# P09_Ethernet.net
KiCad netlist of a schematic drawn in Altium Designer
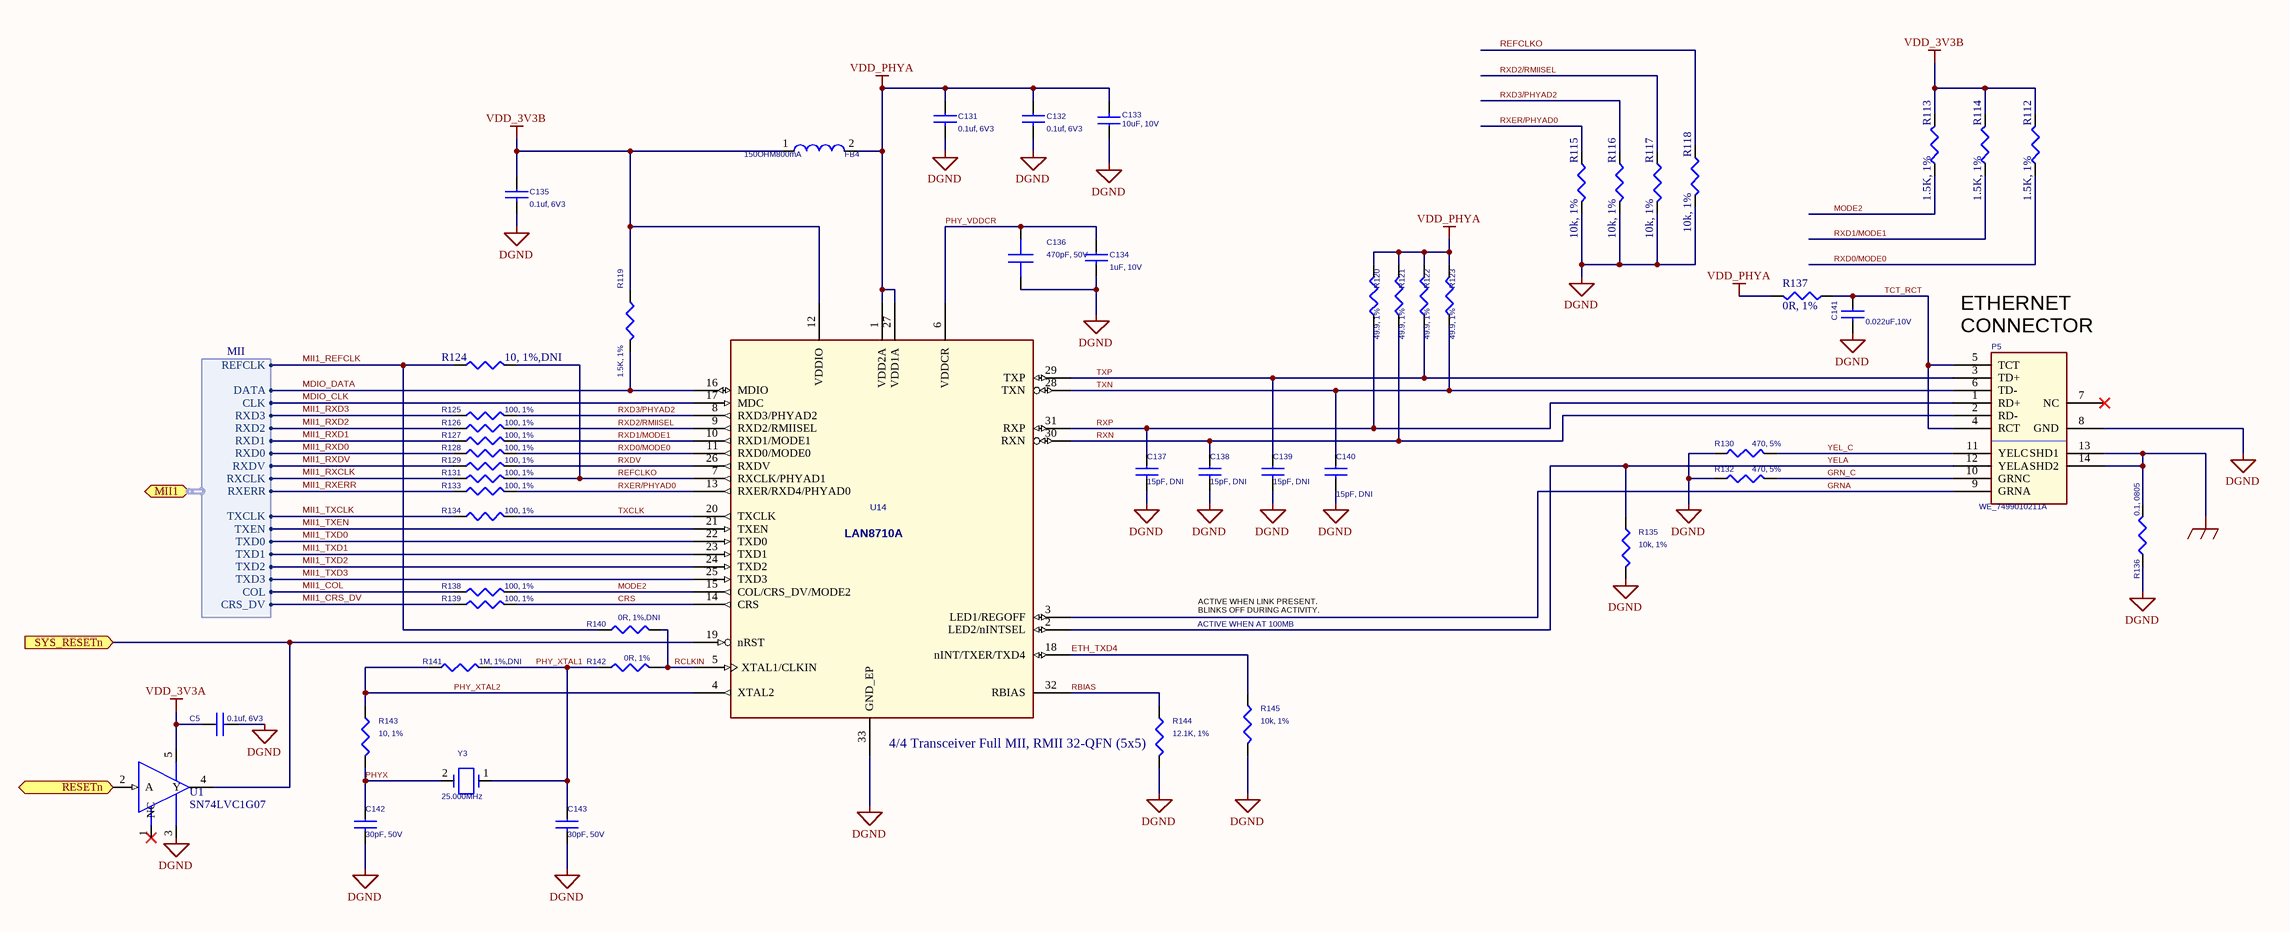
[diagram p0: P09_Ethernet.SchDoc]

(export (version "E")
  (design (tool "Eeschema 10.0.6"))
  (components
    (comp (ref "C5")
      (value "0.1uf, 6V3")
      (footprint "402")
      (description "CAP CER 0.1UF 6.3V 10% X5R 0402")
      (fields
        (field (name "MANUFACTURER") "TDK Corporation")
        (field (name "MANUFACTURER PART NUMBER") "C1005X5R0J104K050BA")
      )
      (libsource (lib "BEAGLEBONEBLACK_REV A5B") (part "CAP_0.1uF_X7R_16V_10% 0402"))
    )
    (comp (ref "C131")
      (value "0.1uf, 6V3")
      (footprint "402")
      (description "CAP CER 0.1UF 6.3V 10% X5R 0402")
      (fields
        (field (name "MANUFACTURER") "TDK Corporation")
        (field (name "MANUFACTURER PART NUMBER") "C1005X5R0J104K050BA")
      )
      (libsource (lib "BEAGLEBONEBLACK_REV A5B") (part "CAP_0.1uF_X7R_16V_10% 0402"))
    )
    (comp (ref "C132")
      (value "0.1uf, 6V3")
      (footprint "402")
      (description "CAP CER 0.1UF 6.3V 10% X5R 0402")
      (fields
        (field (name "MANUFACTURER") "TDK Corporation")
        (field (name "MANUFACTURER PART NUMBER") "C1005X5R0J104K050BA")
      )
      (libsource (lib "BEAGLEBONEBLACK_REV A5B") (part "CAP_0.1uF_X7R_16V_10% 0402"))
    )
    (comp (ref "C133")
      (value "10uF, 10V")
      (footprint "805")
      (description "CAP CER 10UF 10V Y5V 0805")
      (fields
        (field (name "MANUFACTURER") "TDK Corporation")
        (field (name "MANUFACTURER PART NUMBER") "C2012Y5V1A106Z")
      )
      (libsource (lib "BEAGLEBONEBLACK_REV A5B") (part "CAP_4.7uF_X5R_6.3V_10%_0603"))
    )
    (comp (ref "C134")
      (value "1uF, 10V")
      (footprint "402")
      (description "CAP CER 1UF 10V 10% X5R 0402")
      (fields
        (field (name "MANUFACTURER") "AVX Corporation")
        (field (name "MANUFACTURER PART NUMBER") "0402ZD105KAT2A")
      )
      (libsource (lib "BEAGLEBONEBLACK_REV A5B") (part "CAP_1.0UF_X5R_10V_10%_0402"))
    )
    (comp (ref "C135")
      (value "0.1uf, 6V3")
      (footprint "402")
      (description "CAP CER 0.1UF 6.3V 10% X5R 0402")
      (fields
        (field (name "MANUFACTURER") "TDK Corporation")
        (field (name "MANUFACTURER PART NUMBER") "C1005X5R0J104K050BA")
      )
      (libsource (lib "BEAGLEBONEBLACK_REV A5B") (part "CAP_0.1uF_X7R_16V_10% 0402"))
    )
    (comp (ref "C136")
      (value "470pF, 50V")
      (footprint "402")
      (description "CAP CER 470PF 50V 10% X7R 0402")
      (fields
        (field (name "MANUFACTURER") "Murata Electronics North America")
        (field (name "MANUFACTURER PART NUMBER") "GRM155R71H471KA01D")
      )
      (libsource (lib "BEAGLEBONEBLACK_REV A5B") (part "470pF/5%/50V/C0G/0603_0"))
    )
    (comp (ref "C137")
      (value "15pF, DNI")
      (footprint "402")
      (description "CAP CER 15PF 50V 5% NP0 0402")
      (fields
        (field (name "MANUFACTURER") "TDK Corporation")
        (field (name "MANUFACTURER PART NUMBER") "C1005C0G1H150J050BA")
      )
      (libsource (lib "BEAGLEBONEBLACK_REV A5B") (part "CAP_0402_100pF_COG_50V"))
    )
    (comp (ref "C138")
      (value "15pF, DNI")
      (footprint "402")
      (description "CAP CER 15PF 50V 5% NP0 0402")
      (fields
        (field (name "MANUFACTURER") "TDK Corporation")
        (field (name "MANUFACTURER PART NUMBER") "C1005C0G1H150J050BA")
      )
      (libsource (lib "BEAGLEBONEBLACK_REV A5B") (part "CAP_0402_100pF_COG_50V"))
    )
    (comp (ref "C139")
      (value "15pF, DNI")
      (footprint "402")
      (description "CAP CER 15PF 50V 5% NP0 0402")
      (fields
        (field (name "MANUFACTURER") "TDK Corporation")
        (field (name "MANUFACTURER PART NUMBER") "C1005C0G1H150J050BA")
      )
      (libsource (lib "BEAGLEBONEBLACK_REV A5B") (part "CAP_0402_100pF_COG_50V"))
    )
    (comp (ref "C140")
      (value "15pF, DNI")
      (footprint "402")
      (description "CAP CER 15PF 50V 5% NP0 0402")
      (fields
        (field (name "MANUFACTURER") "TDK Corporation")
        (field (name "MANUFACTURER PART NUMBER") "C1005C0G1H150J050BA")
      )
      (libsource (lib "BEAGLEBONEBLACK_REV A5B") (part "CAP_0402_100pF_COG_50V"))
    )
    (comp (ref "C141")
      (value "0.022uF,10V")
      (footprint "402")
      (description "CAP CER 0.022UF 10V 10% X7R 0402")
      (fields
        (field (name "MANUFACTURER") "Taiyo Yuden")
        (field (name "MANUFACTURER PART NUMBER") "LMK105B7223KV-F")
      )
      (libsource (lib "BEAGLEBONEBLACK_REV A5B") (part "CAP_0402_0.1uf_X5R_10V"))
    )
    (comp (ref "C142")
      (value "30pF, 50V")
      (footprint "402")
      (description "CAP CER 30PF 50V 5% NP0 0402")
      (fields
        (field (name "MANUFACTURER") "TDK Corporation")
        (field (name "MANUFACTURER PART NUMBER") "C1005C0G1H300J")
      )
      (libsource (lib "BEAGLEBONEBLACK_REV A5B") (part "CAP_30PF_COG_50V_5%_0402"))
    )
    (comp (ref "C143")
      (value "30pF, 50V")
      (footprint "402")
      (description "CAP CER 30PF 50V 5% NP0 0402")
      (fields
        (field (name "MANUFACTURER") "TDK Corporation")
        (field (name "MANUFACTURER PART NUMBER") "C1005C0G1H300J")
      )
      (libsource (lib "BEAGLEBONEBLACK_REV A5B") (part "CAP_30PF_COG_50V_5%_0402"))
    )
    (comp (ref "FB4")
      (value "150OHM800mA")
      (footprint "SM-7351-IND-0805")
      (description "FERRITE 800MA 150 OHM 0805 SMD")
      (fields (field (name "MFR") "Steward") (field (name "TIINTPARTNUMBER") "1L0010"))
      (libsource (lib "BEAGLEBONEBLACK_REV A5B") (part "FER_180_200_0"))
    )
    (comp (ref "P5")
      (value "WE_7499010211A")
      (description "WE-RJ45 LAN Transformer")
      (libsource (lib "BEAGLEBONEBLACK_REV A5B") (part "CONN_RJ45_MAG_WE_0"))
    )
    (comp (ref "R112")
      (value "1.5K, 1%")
      (footprint "402")
      (description "RES 1.50K OHM 1/16W 1% 0402 SMD")
      (fields
        (field (name "MANUFACTURER") "Yageo")
        (field (name "MANUFACTURER PART NUMBER") "RC0402FR-071K5L")
      )
      (libsource (lib "BEAGLEBONEBLACK_REV A5B") (part "RES_10K_1/16W_1%_0402"))
    )
    (comp (ref "R113")
      (value "1.5K, 1%")
      (footprint "402")
      (description "RES 1.50K OHM 1/16W 1% 0402 SMD")
      (fields
        (field (name "MANUFACTURER") "Yageo")
        (field (name "MANUFACTURER PART NUMBER") "RC0402FR-071K5L")
      )
      (libsource (lib "BEAGLEBONEBLACK_REV A5B") (part "RES_10K_1/16W_1%_0402"))
    )
    (comp (ref "R114")
      (value "1.5K, 1%")
      (footprint "402")
      (description "RES 1.50K OHM 1/16W 1% 0402 SMD")
      (fields
        (field (name "MANUFACTURER") "Yageo")
        (field (name "MANUFACTURER PART NUMBER") "RC0402FR-071K5L")
      )
      (libsource (lib "BEAGLEBONEBLACK_REV A5B") (part "RES_10K_1/16W_1%_0402"))
    )
    (comp (ref "R115")
      (value "10k, 1%")
      (footprint "402")
      (description "RES 10K OHM 1/16W 5% 0402 SMD")
      (fields
        (field (name "MANUFACTURER") "Rohm Semiconductor")
        (field (name "MANUFACTURER PART NUMBER") "MCR01MZPJ103")
      )
      (libsource (lib "BEAGLEBONEBLACK_REV A5B") (part "RES_10K_1/16W_1%_0402"))
    )
    (comp (ref "R116")
      (value "10k, 1%")
      (footprint "402")
      (description "RES 10K OHM 1/16W 5% 0402 SMD")
      (fields
        (field (name "MANUFACTURER") "Rohm Semiconductor")
        (field (name "MANUFACTURER PART NUMBER") "MCR01MZPJ103")
      )
      (libsource (lib "BEAGLEBONEBLACK_REV A5B") (part "RES_10K_1/16W_1%_0402"))
    )
    (comp (ref "R117")
      (value "10k, 1%")
      (footprint "402")
      (description "RES 10K OHM 1/16W 5% 0402 SMD")
      (fields
        (field (name "MANUFACTURER") "Rohm Semiconductor")
        (field (name "MANUFACTURER PART NUMBER") "MCR01MZPJ103")
      )
      (libsource (lib "BEAGLEBONEBLACK_REV A5B") (part "RES_10K_1/16W_1%_0402"))
    )
    (comp (ref "R118")
      (value "10k, 1%")
      (footprint "402")
      (description "RES 10K OHM 1/16W 5% 0402 SMD")
      (fields
        (field (name "MANUFACTURER") "Rohm Semiconductor")
        (field (name "MANUFACTURER PART NUMBER") "MCR01MZPJ103")
      )
      (libsource (lib "BEAGLEBONEBLACK_REV A5B") (part "RES_10K_1/16W_1%_0402"))
    )
    (comp (ref "R119")
      (value "1.5K, 1%")
      (footprint "402")
      (description "RES 1.50K OHM 1/16W 1% 0402 SMD")
      (fields
        (field (name "MANUFACTURER") "Yageo")
        (field (name "MANUFACTURER PART NUMBER") "RC0402FR-071K5L")
      )
      (libsource (lib "BEAGLEBONEBLACK_REV A5B") (part "RES_1.5K_1/16W_5%_0402"))
    )
    (comp (ref "R120")
      (value "49.9, 1%")
      (footprint "402")
      (description "RES 49.9 OHM 1/16W 1% 0402 SMD")
      (fields
        (field (name "MANUFACTURER") "Yageo")
        (field (name "MANUFACTURER PART NUMBER") "RC0402FR-0749R9L")
      )
      (libsource (lib "BEAGLEBONEBLACK_REV A5B") (part "RES_4.7K_0402"))
    )
    (comp (ref "R121")
      (value "49.9, 1%")
      (footprint "402")
      (description "RES 49.9 OHM 1/16W 1% 0402 SMD")
      (fields
        (field (name "MANUFACTURER") "Yageo")
        (field (name "MANUFACTURER PART NUMBER") "RC0402FR-0749R9L")
      )
      (libsource (lib "BEAGLEBONEBLACK_REV A5B") (part "RES_4.7K_0402"))
    )
    (comp (ref "R122")
      (value "49.9, 1%")
      (footprint "402")
      (description "RES 49.9 OHM 1/16W 1% 0402 SMD")
      (fields
        (field (name "MANUFACTURER") "Yageo")
        (field (name "MANUFACTURER PART NUMBER") "RC0402FR-0749R9L")
      )
      (libsource (lib "BEAGLEBONEBLACK_REV A5B") (part "RES_4.7K_0402"))
    )
    (comp (ref "R123")
      (value "49.9, 1%")
      (footprint "402")
      (description "RES 49.9 OHM 1/16W 1% 0402 SMD")
      (fields
        (field (name "MANUFACTURER") "Yageo")
        (field (name "MANUFACTURER PART NUMBER") "RC0402FR-0749R9L")
      )
      (libsource (lib "BEAGLEBONEBLACK_REV A5B") (part "RES_4.7K_0402"))
    )
    (comp (ref "R124")
      (value "10, 1%,DNI")
      (footprint "402")
      (description "Resistor 10Kohm 1/16W 1% 0402")
      (fields
        (field (name "MANUFACTURER") "Stackpole Electronics Inc")
        (field (name "MANUFACTURER PART NUMBER") "RMCF0402FT10R0")
      )
      (libsource (lib "BEAGLEBONEBLACK_REV A5B") (part "RES_10K_1/16W_1%_0402"))
    )
    (comp (ref "R125")
      (value "100, 1%")
      (footprint "402")
      (description "RES 100 OHM 1/10W 5% 0402 SMD")
      (fields
        (field (name "PART#") "Rohm MCR03EZPFX1000")
        (field (name "MANUFACTURER") "Panasonic Electronic Components")
      )
      (libsource (lib "BEAGLEBONEBLACK_REV A5B") (part "100-1/10W-1%-0603_4"))
    )
    (comp (ref "R126")
      (value "100, 1%")
      (footprint "402")
      (description "RES 100 OHM 1/10W 5% 0402 SMD")
      (fields
        (field (name "PART#") "Rohm MCR03EZPFX1000")
        (field (name "MANUFACTURER") "Panasonic Electronic Components")
      )
      (libsource (lib "BEAGLEBONEBLACK_REV A5B") (part "100-1/10W-1%-0603_4"))
    )
    (comp (ref "R127")
      (value "100, 1%")
      (footprint "402")
      (description "RES 100 OHM 1/10W 5% 0402 SMD")
      (fields
        (field (name "MANUFACTURER") "Panasonic Electronic Components")
        (field (name "MANUFACTURER PART NUMBER") "ERJ-2RKF1000X")
      )
      (libsource (lib "BEAGLEBONEBLACK_REV A5B") (part "RES_100_1/10W_5%_0402"))
    )
    (comp (ref "R128")
      (value "100, 1%")
      (footprint "402")
      (description "RES 100 OHM 1/10W 5% 0402 SMD")
      (fields
        (field (name "MANUFACTURER") "Panasonic Electronic Components")
        (field (name "MANUFACTURER PART NUMBER") "ERJ-2RKF1000X")
      )
      (libsource (lib "BEAGLEBONEBLACK_REV A5B") (part "RES_100_1/10W_5%_0402"))
    )
    (comp (ref "R129")
      (value "100, 1%")
      (footprint "402")
      (description "RES 100 OHM 1/10W 5% 0402 SMD")
      (fields
        (field (name "PART#") "Rohm MCR03EZPFX1000")
        (field (name "MANUFACTURER") "Panasonic Electronic Components")
      )
      (libsource (lib "BEAGLEBONEBLACK_REV A5B") (part "100-1/10W-1%-0603_4"))
    )
    (comp (ref "R130")
      (value "470, 5%")
      (footprint "402")
      (description "RES 470 OHM 1/10W 5% 0402 SMD")
      (fields
        (field (name "MANUFACTURER") "Panasonic Electronic Components")
        (field (name "MANUFACTURER PART NUMBER") "ERJ-2GEJ471X")
      )
      (libsource (lib "BEAGLEBONEBLACK_REV A5B") (part "RES_470_1/10W_5%_0402"))
    )
    (comp (ref "R131")
      (value "100, 1%")
      (footprint "402")
      (description "RES 100 OHM 1/10W 5% 0402 SMD")
      (fields
        (field (name "MANUFACTURER") "Panasonic Electronic Components")
        (field (name "MANUFACTURER PART NUMBER") "ERJ-2RKF1000X")
      )
      (libsource (lib "BEAGLEBONEBLACK_REV A5B") (part "RES_100_1/10W_5%_0402"))
    )
    (comp (ref "R132")
      (value "470, 5%")
      (footprint "402")
      (description "RES 470 OHM 1/10W 5% 0402 SMD")
      (fields
        (field (name "MANUFACTURER") "Panasonic Electronic Components")
        (field (name "MANUFACTURER PART NUMBER") "ERJ-2GEJ471X")
      )
      (libsource (lib "BEAGLEBONEBLACK_REV A5B") (part "RES_470_1/10W_5%_0402"))
    )
    (comp (ref "R133")
      (value "100, 1%")
      (footprint "402")
      (description "RES 100 OHM 1/10W 5% 0402 SMD")
      (fields
        (field (name "MANUFACTURER") "Panasonic Electronic Components")
        (field (name "MANUFACTURER PART NUMBER") "ERJ-2RKF1000X")
      )
      (libsource (lib "BEAGLEBONEBLACK_REV A5B") (part "RES_100_1/10W_5%_0402"))
    )
    (comp (ref "R134")
      (value "100, 1%")
      (footprint "402")
      (description "RES 100 OHM 1/10W 5% 0402 SMD")
      (fields (field (name "PART#") "Rohm MCR03EZPFX1000") (field (name "TOLERANCE") "1%"))
      (libsource (lib "BEAGLEBONEBLACK_REV A5B") (part "100-1/10W-1%-0603_4"))
    )
    (comp (ref "R135")
      (value "10k, 1%")
      (footprint "402")
      (description "RES 10K OHM 1/16W 5% 0402 SMD")
      (fields
        (field (name "MANUFACTURER") "Rohm Semiconductor")
        (field (name "MANUFACTURER PART NUMBER") "MCR01MZPJ103")
      )
      (libsource (lib "BEAGLEBONEBLACK_REV A5B") (part "RES_10K_1/16W_1%_0402"))
    )
    (comp (ref "R136")
      (value "0.1, 0805")
      (description "RES .10 OHM 1/8W 5% 0805")
      (fields
        (field (name "MANUFACTURER") "CTS Resistor Products")
        (field (name "MANUFACTURER PART NUMBER") "73L3R10J")
      )
      (libsource (lib "BEAGLEBONEBLACK_REV A5B") (part "RES_0.1_0805"))
    )
    (comp (ref "R137")
      (value "0R, 1%")
      (footprint "402")
      (description "RES 0.0 OHM 1/16W 0402 SMD")
      (fields
        (field (name "MANUFACTURER") "Yageo")
        (field (name "MANUFACTURER PART NUMBER") "RC0402JR-070RL")
      )
      (libsource (lib "BEAGLEBONEBLACK_REV A5B") (part "RES_0_1/16W_1%_0402"))
    )
    (comp (ref "R138")
      (value "100, 1%")
      (footprint "402")
      (description "RES 100 OHM 1/10W 5% 0402 SMD")
      (fields (field (name "PART#") "Rohm MCR03EZPFX1000") (field (name "TOLERANCE") "1%"))
      (libsource (lib "BEAGLEBONEBLACK_REV A5B") (part "100-1/10W-1%-0603_4"))
    )
    (comp (ref "R139")
      (value "100, 1%")
      (footprint "402")
      (description "RES 100 OHM 1/10W 5% 0402 SMD")
      (fields
        (field (name "MANUFACTURER") "Panasonic Electronic Components")
        (field (name "MANUFACTURER PART NUMBER") "ERJ-2RKF1000X")
      )
      (libsource (lib "BEAGLEBONEBLACK_REV A5B") (part "RES_100_1/10W_5%_0402"))
    )
    (comp (ref "R140")
      (value "0R, 1%,DNI")
      (footprint "402")
      (description "RES 0.0 OHM 1/16W 0402 SMD")
      (fields
        (field (name "MANUFACTURER") "Yageo")
        (field (name "MANUFACTURER PART NUMBER") "RC0402JR-070RL")
      )
      (libsource (lib "BEAGLEBONEBLACK_REV A5B") (part "RES_0_1/16W_1%_0402"))
    )
    (comp (ref "R141")
      (value "1M, 1%,DNI")
      (footprint "402")
      (description "RES 1M OHM 1/16W 1% 0402 SMD")
      (fields
        (field (name "MANUFACTURER") "Stackpole Electronics Inc")
        (field (name "MANUFACTURER PART NUMBER") "RMCF0402FT1M00")
      )
      (libsource (lib "BEAGLEBONEBLACK_REV A5B") (part "RES_1M_1/16W_1%_0402"))
    )
    (comp (ref "R142")
      (value "0R, 1%")
      (footprint "402")
      (description "RES 0.0 OHM 1/16W 0402 SMD")
      (fields
        (field (name "MANUFACTURER") "Yageo")
        (field (name "MANUFACTURER PART NUMBER") "RC0402JR-070RL")
      )
      (libsource (lib "BEAGLEBONEBLACK_REV A5B") (part "RES_0_1/16W_1%_0402"))
    )
    (comp (ref "R143")
      (value "10, 1%")
      (footprint "402")
      (description "RES 10 OHM 1/16W 1% 0402 SMD")
      (fields
        (field (name "MANUFACTURER") "Stackpole Electronics Inc")
        (field (name "MANUFACTURER PART NUMBER") "RMCF0402FT10R0")
      )
      (libsource (lib "BEAGLEBONEBLACK_REV A5B") (part "RES_10K_1/16W_1%_0402"))
    )
    (comp (ref "R144")
      (value "12.1K, 1%")
      (footprint "402")
      (description "RES 12.1K OHM 1/16W 1% 0402 SMD")
      (fields
        (field (name "MANUFACTURER") "Yageo")
        (field (name "MANUFACTURER PART NUMBER") "RC0402FR-0712K1L")
      )
      (libsource (lib "BEAGLEBONEBLACK_REV A5B") (part "RES_12.1K_1/16W_1%_0402"))
    )
    (comp (ref "R145")
      (value "10k, 1%")
      (footprint "402")
      (description "RES 10K OHM 1/16W 5% 0402 SMD")
      (fields
        (field (name "MANUFACTURER") "Rohm Semiconductor")
        (field (name "MANUFACTURER PART NUMBER") "MCR01MZPJ103")
      )
      (libsource (lib "BEAGLEBONEBLACK_REV A5B") (part "RES_10K_1/16W_1%_0402"))
    )
    (comp (ref "U1")
      (value "SN74LVC1G07")
      (footprint "DCK5_2P15X1P4")
      (description "IC BUFFER SINGLE 1INPUT SC705")
      (fields
        (field (name "MANUFACTURER") "Texas Instruments")
        (field (name "MANUFACTURER PART NUMBER") "SN74LVC1G06DCKTG4")
      )
      (libsource (lib "BEAGLEBONEBLACK_REV A5B_1") (part "SN74LVC1G07DCK"))
    )
    (comp (ref "U14")
      (value "LAN8710A")
      (footprint "QFN32_5X5MM_EP3P3MM")
      (description "Ethernet ICs 10/100 Ethernet XCVR w/HPAutoMDIX FlexPwr")
      (fields (field (name "PART#") "SMSC LAN8710A-EZK") (field (name "MANUFACTURER") "Microchip Technology"))
      (libsource (lib "BEAGLEBONEBLACK_REV A5B") (part "LAN8710 QFN32_1"))
    )
    (comp (ref "Y3")
      (value "25.000MHz")
      (footprint "XTAL150SMD_125X196")
      (fields
        (field (name "MANUFACTURER") "Abracon Corporation")
        (field (name "MANUFACTURER PART NUMBER") "ABM3-25.000MHZ-B2-T")
      )
      (libsource (lib "BEAGLEBONEBLACK_REV A5B") (part "Suntsu ITEMP 25MHz _0.005% 20pf"))
    )
  )
  (nets
    (net (code "2") (name "/CRS") (class "Default")
      (node (ref "R139") (pin "2") (pinfunction "2_2") (pintype "passive"))
      (node (ref "U14") (pin "14") (pinfunction "CRS_14") (pintype "output"))
    )
    (net (code "3") (name "/ETH_TXD4") (class "Default")
      (node (ref "R145") (pin "1") (pinfunction "1_1") (pintype "passive"))
      (node (ref "U14") (pin "18") (pinfunction "nINT/TXER/TXD4_18") (pintype "bidirectional"))
    )
    (net (code "4") (name "/GRNA") (class "Default")
      (node (ref "P5") (pin "9") (pinfunction "GRNA_9") (pintype "passive"))
      (node (ref "U14") (pin "3") (pinfunction "LED1/REGOFF_3") (pintype "bidirectional"))
    )
    (net (code "5") (name "/GRN_C") (class "Default")
      (node (ref "P5") (pin "10") (pinfunction "GRNC_10") (pintype "passive"))
      (node (ref "R132") (pin "2") (pinfunction "2_2") (pintype "passive"))
    )
    (net (code "6") (name "/MDIO_CLK") (class "Default")
      (node (ref "U14") (pin "17") (pinfunction "MDC_17") (pintype "input"))
    )
    (net (code "7") (name "/MDIO_DATA") (class "Default")
      (node (ref "R119") (pin "2") (pinfunction "2_2") (pintype "passive"))
      (node (ref "U14") (pin "16") (pinfunction "MDIO_16") (pintype "bidirectional"))
    )
    (net (code "8") (name "/MII1_COL") (class "Default")
      (node (ref "R138") (pin "1") (pinfunction "1_1") (pintype "passive"))
    )
    (net (code "9") (name "/MII1_CRS_DV") (class "Default")
      (node (ref "R139") (pin "1") (pinfunction "1_1") (pintype "passive"))
    )
    (net (code "10") (name "/MII1_REFCLK") (class "Default")
      (node (ref "R124") (pin "1") (pinfunction "1_1") (pintype "passive"))
      (node (ref "R140") (pin "1") (pinfunction "1_1") (pintype "passive"))
    )
    (net (code "11") (name "/MII1_RXCLK") (class "Default")
      (node (ref "R131") (pin "1") (pinfunction "1_1") (pintype "passive"))
    )
    (net (code "12") (name "/MII1_RXD0") (class "Default")
      (node (ref "R128") (pin "1") (pinfunction "1_1") (pintype "passive"))
    )
    (net (code "13") (name "/MII1_RXD1") (class "Default")
      (node (ref "R127") (pin "1") (pinfunction "1_1") (pintype "passive"))
    )
    (net (code "14") (name "/MII1_RXD2") (class "Default")
      (node (ref "R126") (pin "1") (pinfunction "1_1") (pintype "passive"))
    )
    (net (code "15") (name "/MII1_RXD3") (class "Default")
      (node (ref "R125") (pin "1") (pinfunction "1_1") (pintype "passive"))
    )
    (net (code "16") (name "/MII1_RXDV") (class "Default")
      (node (ref "R129") (pin "1") (pinfunction "1_1") (pintype "passive"))
    )
    (net (code "17") (name "/MII1_RXERR") (class "Default")
      (node (ref "R133") (pin "1") (pinfunction "1_1") (pintype "passive"))
    )
    (net (code "18") (name "/MII1_TXCLK") (class "Default")
      (node (ref "R134") (pin "1") (pinfunction "1_1") (pintype "passive"))
    )
    (net (code "19") (name "/MII1_TXD0") (class "Default")
      (node (ref "U14") (pin "22") (pinfunction "TXD0_22") (pintype "input"))
    )
    (net (code "20") (name "/MII1_TXD1") (class "Default")
      (node (ref "U14") (pin "23") (pinfunction "TXD1_23") (pintype "input"))
    )
    (net (code "21") (name "/MII1_TXD2") (class "Default")
      (node (ref "U14") (pin "24") (pinfunction "TXD2_24") (pintype "input"))
    )
    (net (code "22") (name "/MII1_TXD3") (class "Default")
      (node (ref "U14") (pin "25") (pinfunction "TXD3_25") (pintype "input"))
    )
    (net (code "23") (name "/MII1_TXEN") (class "Default")
      (node (ref "U14") (pin "21") (pinfunction "TXEN_21") (pintype "input"))
    )
    (net (code "24") (name "/MODE2") (class "Default")
      (node (ref "R113") (pin "1") (pinfunction "1_1") (pintype "passive"))
      (node (ref "R138") (pin "2") (pinfunction "2_2") (pintype "passive"))
      (node (ref "U14") (pin "15") (pinfunction "COL/CRS_DV/MODE2_15") (pintype "output"))
    )
    (net (code "25") (name "/PHYX") (class "Default")
      (node (ref "C142") (pin "1") (pinfunction "1_1") (pintype "passive"))
      (node (ref "R143") (pin "2") (pinfunction "2_2") (pintype "passive"))
      (node (ref "Y3") (pin "2") (pinfunction "2_2") (pintype "passive"))
    )
    (net (code "26") (name "/PHY_VDDCR") (class "Default")
      (node (ref "C134") (pin "1") (pinfunction "1_1") (pintype "passive"))
      (node (ref "C136") (pin "1") (pinfunction "1_1") (pintype "passive"))
      (node (ref "U14") (pin "6") (pinfunction "VDDCR_6") (pintype "power_in"))
    )
    (net (code "27") (name "/PHY_XTAL1") (class "Default")
      (node (ref "C143") (pin "1") (pinfunction "1_1") (pintype "passive"))
      (node (ref "R141") (pin "2") (pinfunction "2_2") (pintype "passive"))
      (node (ref "R142") (pin "1") (pinfunction "1_1") (pintype "passive"))
      (node (ref "Y3") (pin "1") (pinfunction "1_1") (pintype "passive"))
    )
    (net (code "28") (name "/PHY_XTAL2") (class "Default")
      (node (ref "R141") (pin "1") (pinfunction "1_1") (pintype "passive"))
      (node (ref "R143") (pin "1") (pinfunction "1_1") (pintype "passive"))
      (node (ref "U14") (pin "4") (pinfunction "XTAL2_4") (pintype "output"))
    )
    (net (code "29") (name "/RBIAS") (class "Default")
      (node (ref "R144") (pin "1") (pinfunction "1_1") (pintype "passive"))
      (node (ref "U14") (pin "32") (pinfunction "RBIAS_32") (pintype "passive"))
    )
    (net (code "30") (name "/RCLKIN") (class "Default")
      (node (ref "R140") (pin "2") (pinfunction "2_2") (pintype "passive"))
      (node (ref "R142") (pin "2") (pinfunction "2_2") (pintype "passive"))
      (node (ref "U14") (pin "5") (pinfunction "XTAL1/CLKIN_5") (pintype "input"))
    )
    (net (code "31") (name "/REFCLKO") (class "Default")
      (node (ref "R118") (pin "1") (pinfunction "1_1") (pintype "passive"))
      (node (ref "R124") (pin "2") (pinfunction "2_2") (pintype "passive"))
      (node (ref "R131") (pin "2") (pinfunction "2_2") (pintype "passive"))
      (node (ref "U14") (pin "7") (pinfunction "RXCLK/PHYAD1_7") (pintype "output"))
    )
    (net (code "32") (name "/RESETn") (class "Default")
      (node (ref "U1") (pin "2") (pinfunction "A_2") (pintype "input"))
    )
    (net (code "33") (name "/RXD0{slash}MODE0") (class "Default")
      (node (ref "R112") (pin "1") (pinfunction "1_1") (pintype "passive"))
      (node (ref "R128") (pin "2") (pinfunction "2_2") (pintype "passive"))
      (node (ref "U14") (pin "11") (pinfunction "RXD0/MODE0_11") (pintype "output"))
    )
    (net (code "34") (name "/RXD1{slash}MODE1") (class "Default")
      (node (ref "R114") (pin "1") (pinfunction "1_1") (pintype "passive"))
      (node (ref "R127") (pin "2") (pinfunction "2_2") (pintype "passive"))
      (node (ref "U14") (pin "10") (pinfunction "RXD1/MODE1_10") (pintype "output"))
    )
    (net (code "35") (name "/RXD2{slash}RMIISEL") (class "Default")
      (node (ref "R117") (pin "1") (pinfunction "1_1") (pintype "passive"))
      (node (ref "R126") (pin "2") (pinfunction "2_2") (pintype "passive"))
      (node (ref "U14") (pin "9") (pinfunction "RXD2/RMIISEL_9") (pintype "output"))
    )
    (net (code "36") (name "/RXD3{slash}PHYAD2") (class "Default")
      (node (ref "R116") (pin "1") (pinfunction "1_1") (pintype "passive"))
      (node (ref "R125") (pin "2") (pinfunction "2_2") (pintype "passive"))
      (node (ref "U14") (pin "8") (pinfunction "RXD3/PHYAD2_8") (pintype "output"))
    )
    (net (code "37") (name "/RXDV") (class "Default")
      (node (ref "R129") (pin "2") (pinfunction "2_2") (pintype "passive"))
      (node (ref "U14") (pin "26") (pinfunction "RXDV_26") (pintype "output"))
    )
    (net (code "38") (name "/RXER{slash}PHYAD0") (class "Default")
      (node (ref "R115") (pin "1") (pinfunction "1_1") (pintype "passive"))
      (node (ref "R133") (pin "2") (pinfunction "2_2") (pintype "passive"))
      (node (ref "U14") (pin "13") (pinfunction "RXER/RXD4/PHYAD0_13") (pintype "output"))
    )
    (net (code "39") (name "/RXN") (class "Default")
      (node (ref "C138") (pin "1") (pinfunction "1_1") (pintype "passive"))
      (node (ref "P5") (pin "2") (pinfunction "RD-_2") (pintype "passive"))
      (node (ref "R121") (pin "1") (pinfunction "1_1") (pintype "passive"))
      (node (ref "U14") (pin "30") (pinfunction "RXN_30") (pintype "bidirectional"))
    )
    (net (code "40") (name "/RXP") (class "Default")
      (node (ref "C137") (pin "1") (pinfunction "1_1") (pintype "passive"))
      (node (ref "P5") (pin "1") (pinfunction "RD+_1") (pintype "passive"))
      (node (ref "R120") (pin "1") (pinfunction "1_1") (pintype "passive"))
      (node (ref "U14") (pin "31") (pinfunction "RXP_31") (pintype "bidirectional"))
    )
    (net (code "41") (name "/SYS_RESETn") (class "Default")
      (node (ref "U1") (pin "4") (pinfunction "Y_4") (pintype "open_collector"))
      (node (ref "U14") (pin "19") (pinfunction "nRST_19") (pintype "input"))
    )
    (net (code "42") (name "/TCT_RCT") (class "Default")
      (node (ref "C141") (pin "1") (pinfunction "1_1") (pintype "passive"))
      (node (ref "P5") (pin "4") (pinfunction "RCT_4") (pintype "passive"))
      (node (ref "P5") (pin "5") (pinfunction "TCT_5") (pintype "passive"))
      (node (ref "R137") (pin "1") (pinfunction "1_1") (pintype "passive"))
    )
    (net (code "43") (name "/TXCLK") (class "Default")
      (node (ref "R134") (pin "2") (pinfunction "2_2") (pintype "passive"))
      (node (ref "U14") (pin "20") (pinfunction "TXCLK_20") (pintype "output"))
    )
    (net (code "44") (name "/TXN") (class "Default")
      (node (ref "C140") (pin "1") (pinfunction "1_1") (pintype "passive"))
      (node (ref "P5") (pin "6") (pinfunction "TD-_6") (pintype "passive"))
      (node (ref "R123") (pin "1") (pinfunction "1_1") (pintype "passive"))
      (node (ref "U14") (pin "28") (pinfunction "TXN_28") (pintype "bidirectional"))
    )
    (net (code "45") (name "/TXP") (class "Default")
      (node (ref "C139") (pin "1") (pinfunction "1_1") (pintype "passive"))
      (node (ref "P5") (pin "3") (pinfunction "TD+_3") (pintype "passive"))
      (node (ref "R122") (pin "1") (pinfunction "1_1") (pintype "passive"))
      (node (ref "U14") (pin "29") (pinfunction "TXP_29") (pintype "bidirectional"))
    )
    (net (code "46") (name "/YELA") (class "Default")
      (node (ref "P5") (pin "12") (pinfunction "YELA_12") (pintype "passive"))
      (node (ref "R135") (pin "1") (pinfunction "1_1") (pintype "passive"))
      (node (ref "U14") (pin "2") (pinfunction "LED2/nINTSEL_2") (pintype "bidirectional"))
    )
    (net (code "47") (name "/YEL_C") (class "Default")
      (node (ref "P5") (pin "11") (pinfunction "YELC_11") (pintype "passive"))
      (node (ref "R130") (pin "2") (pinfunction "2_2") (pintype "passive"))
    )
    (net (code "49") (name "DGND") (class "Default")
      (node (ref "C131") (pin "2") (pinfunction "2_2") (pintype "passive"))
      (node (ref "C132") (pin "2") (pinfunction "2_2") (pintype "passive"))
      (node (ref "C133") (pin "1") (pinfunction "1_1") (pintype "passive"))
      (node (ref "C134") (pin "2") (pinfunction "2_2") (pintype "passive"))
      (node (ref "C135") (pin "2") (pinfunction "2_2") (pintype "passive"))
      (node (ref "C136") (pin "2") (pinfunction "2_2") (pintype "passive"))
      (node (ref "C137") (pin "2") (pinfunction "2_2") (pintype "passive"))
      (node (ref "C138") (pin "2") (pinfunction "2_2") (pintype "passive"))
      (node (ref "C139") (pin "2") (pinfunction "2_2") (pintype "passive"))
      (node (ref "C140") (pin "2") (pinfunction "2_2") (pintype "passive"))
      (node (ref "C141") (pin "2") (pinfunction "2_2") (pintype "passive"))
      (node (ref "C142") (pin "2") (pinfunction "2_2") (pintype "passive"))
      (node (ref "C143") (pin "2") (pinfunction "2_2") (pintype "passive"))
      (node (ref "C5") (pin "2") (pinfunction "2_2") (pintype "passive"))
      (node (ref "P5") (pin "8") (pinfunction "GND_8") (pintype "passive"))
      (node (ref "R115") (pin "2") (pinfunction "2_2") (pintype "passive"))
      (node (ref "R116") (pin "2") (pinfunction "2_2") (pintype "passive"))
      (node (ref "R117") (pin "2") (pinfunction "2_2") (pintype "passive"))
      (node (ref "R118") (pin "2") (pinfunction "2_2") (pintype "passive"))
      (node (ref "R130") (pin "1") (pinfunction "1_1") (pintype "passive"))
      (node (ref "R132") (pin "1") (pinfunction "1_1") (pintype "passive"))
      (node (ref "R135") (pin "2") (pinfunction "2_2") (pintype "passive"))
      (node (ref "R136") (pin "1") (pinfunction "1_1") (pintype "passive"))
      (node (ref "R144") (pin "2") (pinfunction "2_2") (pintype "passive"))
      (node (ref "R145") (pin "2") (pinfunction "2_2") (pintype "passive"))
      (node (ref "U1") (pin "3") (pinfunction "GND_3") (pintype "power_in"))
      (node (ref "U14") (pin "33") (pinfunction "GND_EP_33") (pintype "power_in"))
    )
    (net (code "50") (name "GND_EARTH") (class "Default")
      (node (ref "P5") (pin "13") (pinfunction "SHD1_13") (pintype "passive"))
      (node (ref "P5") (pin "14") (pinfunction "SHD2_14") (pintype "passive"))
      (node (ref "R136") (pin "2") (pinfunction "2_2") (pintype "passive"))
    )
    (net (code "51") (name "VDD_3V3A") (class "Default")
      (node (ref "C5") (pin "1") (pinfunction "1_1") (pintype "passive"))
      (node (ref "U1") (pin "5") (pinfunction "VCC_5") (pintype "power_in"))
    )
    (net (code "52") (name "VDD_3V3B") (class "Default")
      (node (ref "C135") (pin "1") (pinfunction "1_1") (pintype "passive"))
      (node (ref "FB4") (pin "1") (pinfunction "1_1") (pintype "passive"))
      (node (ref "R112") (pin "2") (pinfunction "2_2") (pintype "passive"))
      (node (ref "R113") (pin "2") (pinfunction "2_2") (pintype "passive"))
      (node (ref "R114") (pin "2") (pinfunction "2_2") (pintype "passive"))
      (node (ref "R119") (pin "1") (pinfunction "1_1") (pintype "passive"))
      (node (ref "U14") (pin "12") (pinfunction "VDDIO_12") (pintype "power_in"))
    )
    (net (code "53") (name "VDD_PHYA") (class "Default")
      (node (ref "C131") (pin "1") (pinfunction "1_1") (pintype "passive"))
      (node (ref "C132") (pin "1") (pinfunction "1_1") (pintype "passive"))
      (node (ref "C133") (pin "2") (pinfunction "2_2") (pintype "passive"))
      (node (ref "FB4") (pin "2") (pinfunction "2_2") (pintype "passive"))
      (node (ref "R120") (pin "2") (pinfunction "2_2") (pintype "passive"))
      (node (ref "R121") (pin "2") (pinfunction "2_2") (pintype "passive"))
      (node (ref "R122") (pin "2") (pinfunction "2_2") (pintype "passive"))
      (node (ref "R123") (pin "2") (pinfunction "2_2") (pintype "passive"))
      (node (ref "R137") (pin "2") (pinfunction "2_2") (pintype "passive"))
      (node (ref "U14") (pin "1") (pinfunction "VDD2A_1") (pintype "power_in"))
      (node (ref "U14") (pin "27") (pinfunction "VDD1A_27") (pintype "power_in"))
    )
    (net (code "54") (name "unconnected-(P5-NC-Pad7)") (class "Default")
      (node (ref "P5") (pin "7") (pinfunction "NC_7") (pintype "passive+no_connect"))
    )
    (net (code "55") (name "unconnected-(U1-NC-Pad1)") (class "Default")
      (node (ref "U1") (pin "1") (pinfunction "NC_1") (pintype "passive+no_connect"))
    )
  )
)
